# kitchenset19.net
KiCad netlist of a schematic drawn in EAGLE
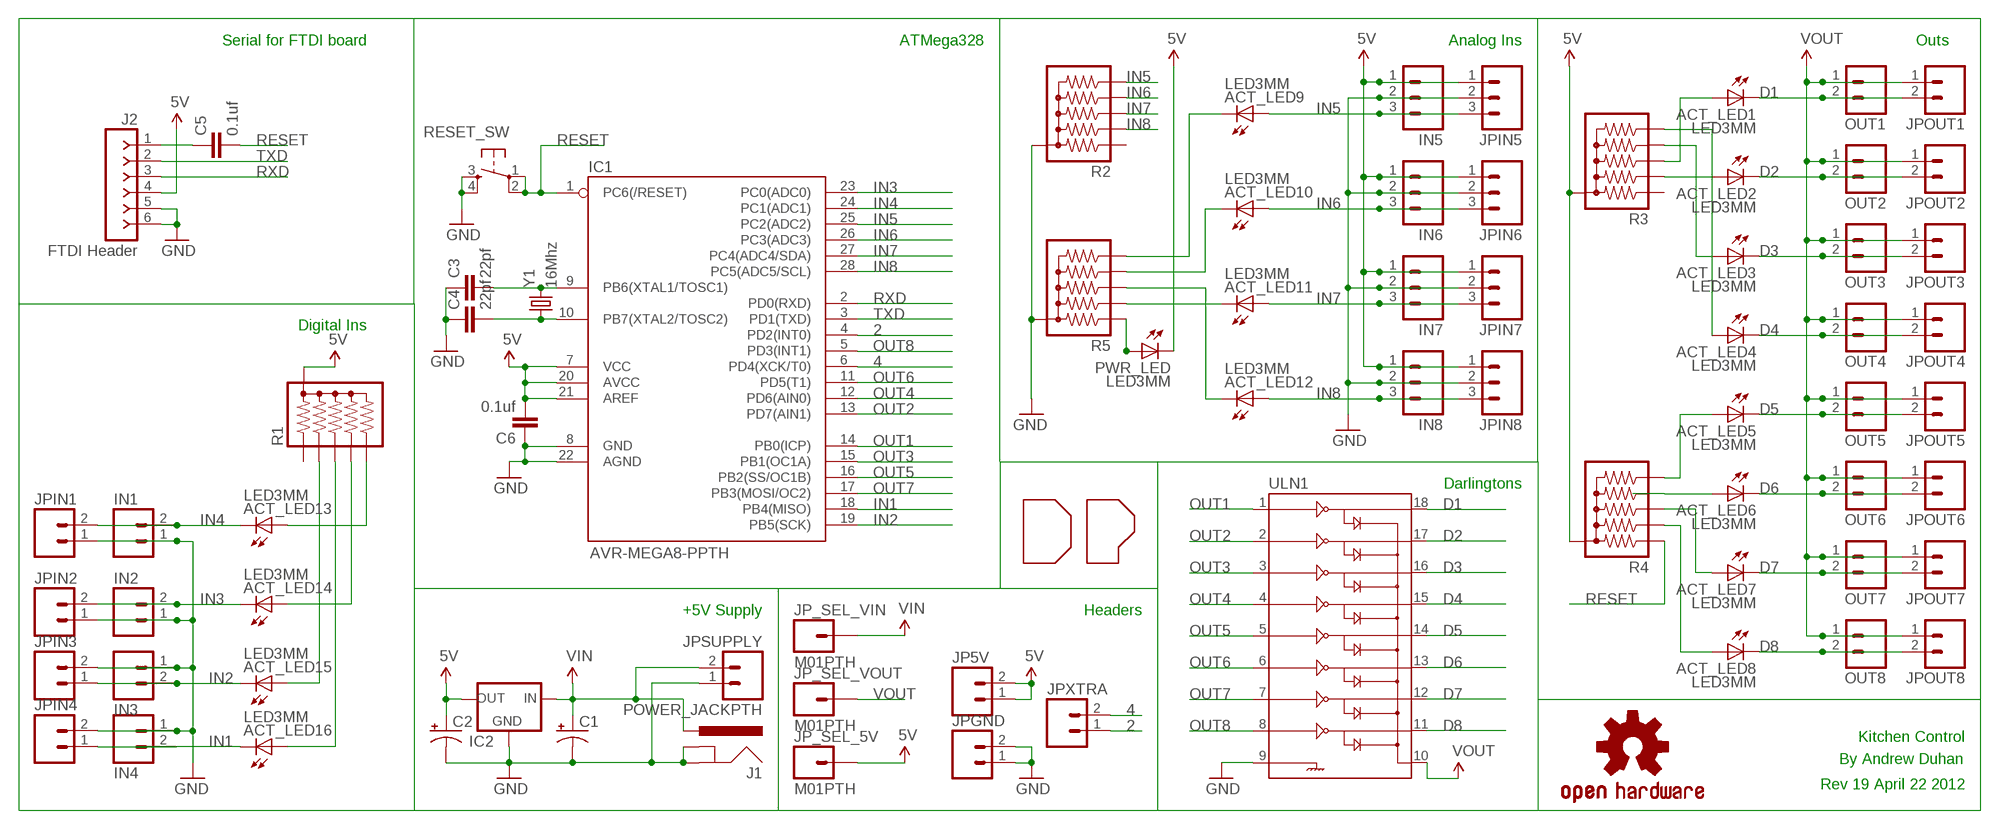
[diagram p0: schematic, sheet 1]

(export (version "E")
  (design (tool "Eeschema 10.0.6"))
  (components
    (comp (ref "ACT_LED1")
      (value "LED3MM")
      (footprint "eagle-import:LED3MM-POL")
      (libsource (lib "eagle-import") (part "LED3MM"))
    )
    (comp (ref "ACT_LED2")
      (value "LED3MM")
      (footprint "eagle-import:LED3MM-POL")
      (libsource (lib "eagle-import") (part "LED3MM"))
    )
    (comp (ref "ACT_LED3")
      (value "LED3MM")
      (footprint "eagle-import:LED3MM-POL")
      (libsource (lib "eagle-import") (part "LED3MM"))
    )
    (comp (ref "ACT_LED4")
      (value "LED3MM")
      (footprint "eagle-import:LED3MM-POL")
      (libsource (lib "eagle-import") (part "LED3MM"))
    )
    (comp (ref "ACT_LED5")
      (value "LED3MM")
      (footprint "eagle-import:LED3MM-POL")
      (libsource (lib "eagle-import") (part "LED3MM"))
    )
    (comp (ref "ACT_LED6")
      (value "LED3MM")
      (footprint "eagle-import:LED3MM-POL")
      (libsource (lib "eagle-import") (part "LED3MM"))
    )
    (comp (ref "ACT_LED7")
      (value "LED3MM")
      (footprint "eagle-import:LED3MM-POL")
      (libsource (lib "eagle-import") (part "LED3MM"))
    )
    (comp (ref "ACT_LED8")
      (value "LED3MM")
      (footprint "eagle-import:LED3MM-POL")
      (libsource (lib "eagle-import") (part "LED3MM"))
    )
    (comp (ref "ACT_LED9")
      (value "LED3MM")
      (footprint "eagle-import:LED3MM-POL")
      (libsource (lib "eagle-import") (part "LED3MM"))
    )
    (comp (ref "ACT_LED10")
      (value "LED3MM")
      (footprint "eagle-import:LED3MM-POL")
      (libsource (lib "eagle-import") (part "LED3MM"))
    )
    (comp (ref "ACT_LED11")
      (value "LED3MM")
      (footprint "eagle-import:LED3MM-POL")
      (libsource (lib "eagle-import") (part "LED3MM"))
    )
    (comp (ref "ACT_LED12")
      (value "LED3MM")
      (footprint "eagle-import:LED3MM-POL")
      (libsource (lib "eagle-import") (part "LED3MM"))
    )
    (comp (ref "ACT_LED13")
      (value "LED3MM")
      (footprint "eagle-import:LED3MM-POL")
      (libsource (lib "eagle-import") (part "LED3MM"))
    )
    (comp (ref "ACT_LED14")
      (value "LED3MM")
      (footprint "eagle-import:LED3MM-POL")
      (libsource (lib "eagle-import") (part "LED3MM"))
    )
    (comp (ref "ACT_LED15")
      (value "LED3MM")
      (footprint "eagle-import:LED3MM-POL")
      (libsource (lib "eagle-import") (part "LED3MM"))
    )
    (comp (ref "ACT_LED16")
      (value "LED3MM")
      (footprint "eagle-import:LED3MM-POL")
      (libsource (lib "eagle-import") (part "LED3MM"))
    )
    (comp (ref "C1")
      (value "CAP_POLPTH4")
      (footprint "eagle-import:CPOL-RADIAL-1000UF-25V")
      (libsource (lib "eagle-import") (part "CAP_POLPTH4"))
    )
    (comp (ref "C2")
      (value "CAP_POLPTH4")
      (footprint "eagle-import:CPOL-RADIAL-1000UF-25V")
      (libsource (lib "eagle-import") (part "CAP_POLPTH4"))
    )
    (comp (ref "C3")
      (value "22pf")
      (footprint "eagle-import:CAP-PTH-SMALL")
      (libsource (lib "eagle-import") (part "CAPPTH"))
    )
    (comp (ref "C4")
      (value "22pf")
      (footprint "eagle-import:CAP-PTH-SMALL")
      (libsource (lib "eagle-import") (part "CAPPTH"))
    )
    (comp (ref "C5")
      (value "0.1uf")
      (footprint "eagle-import:CAP-PTH-SMALL")
      (libsource (lib "eagle-import") (part "CAPPTH"))
    )
    (comp (ref "C6")
      (value "0.1uf")
      (footprint "eagle-import:CAP-PTH-SMALL")
      (libsource (lib "eagle-import") (part "CAPPTH"))
    )
    (comp (ref "IC1")
      (value "AVR-MEGA8-PPTH")
      (footprint "eagle-import:DIL28-3")
      (libsource (lib "eagle-import") (part "AVR-MEGA8-PPTH"))
    )
    (comp (ref "IC2")
      (value "V_REG_78XXSIDE")
      (footprint "eagle-import:78XXL")
      (libsource (lib "eagle-import") (part "V_REG_78XXSIDE"))
    )
    (comp (ref "IN1")
      (value "M02JST-PTH-2")
      (footprint "eagle-import:JST-2-PTH")
      (libsource (lib "eagle-import") (part "SparkFun-Connectors_M02JST-PTH-2"))
    )
    (comp (ref "IN2")
      (value "M02JST-PTH-2")
      (footprint "eagle-import:JST-2-PTH")
      (libsource (lib "eagle-import") (part "SparkFun-Connectors_M02JST-PTH-2"))
    )
    (comp (ref "IN3")
      (value "M02JST-PTH-2")
      (footprint "eagle-import:JST-2-PTH")
      (libsource (lib "eagle-import") (part "M02JST-PTH-2"))
    )
    (comp (ref "IN4")
      (value "M02JST-PTH-2")
      (footprint "eagle-import:JST-2-PTH")
      (libsource (lib "eagle-import") (part "M02JST-PTH-2"))
    )
    (comp (ref "IN5")
      (value "M03JST-PTH")
      (footprint "eagle-import:JST-3-PTH")
      (libsource (lib "eagle-import") (part "M03JST-PTH"))
    )
    (comp (ref "IN6")
      (value "M03JST-PTH")
      (footprint "eagle-import:JST-3-PTH")
      (libsource (lib "eagle-import") (part "M03JST-PTH"))
    )
    (comp (ref "IN7")
      (value "M03JST-PTH")
      (footprint "eagle-import:JST-3-PTH")
      (libsource (lib "eagle-import") (part "M03JST-PTH"))
    )
    (comp (ref "IN8")
      (value "M03JST-PTH")
      (footprint "eagle-import:JST-3-PTH")
      (libsource (lib "eagle-import") (part "M03JST-PTH"))
    )
    (comp (ref "J1")
      (value "POWER_JACKPTH")
      (footprint "eagle-import:POWER_JACK_PTH")
      (libsource (lib "eagle-import") (part "POWER_JACKPTH"))
    )
    (comp (ref "J2")
      (value "FTDI Header")
      (footprint "eagle-import:SIP-100-06-32Y")
      (libsource (lib "eagle-import") (part "F-1X06-SIP-100-32Y"))
    )
    (comp (ref "JP5V")
      (value "M02PTH")
      (footprint "eagle-import:1X02")
      (libsource (lib "eagle-import") (part "M02PTH"))
    )
    (comp (ref "JPGND")
      (value "M02PTH")
      (footprint "eagle-import:1X02")
      (libsource (lib "eagle-import") (part "M02PTH"))
    )
    (comp (ref "JPIN1")
      (value "M02PTH")
      (footprint "eagle-import:1X02")
      (libsource (lib "eagle-import") (part "SparkFun-Connectors_M02PTH"))
    )
    (comp (ref "JPIN2")
      (value "M02PTH")
      (footprint "eagle-import:1X02")
      (libsource (lib "eagle-import") (part "SparkFun-Connectors_M02PTH"))
    )
    (comp (ref "JPIN3")
      (value "M02PTH")
      (footprint "eagle-import:1X02")
      (libsource (lib "eagle-import") (part "SparkFun-Connectors_M02PTH"))
    )
    (comp (ref "JPIN4")
      (value "M02PTH")
      (footprint "eagle-import:1X02")
      (libsource (lib "eagle-import") (part "SparkFun-Connectors_M02PTH"))
    )
    (comp (ref "JPIN5")
      (value "M03PTH")
      (footprint "eagle-import:1X03")
      (libsource (lib "eagle-import") (part "SparkFun-Connectors_M03PTH"))
    )
    (comp (ref "JPIN6")
      (value "M03PTH")
      (footprint "eagle-import:1X03")
      (libsource (lib "eagle-import") (part "SparkFun-Connectors_M03PTH"))
    )
    (comp (ref "JPIN7")
      (value "M03PTH")
      (footprint "eagle-import:1X03")
      (libsource (lib "eagle-import") (part "SparkFun-Connectors_M03PTH"))
    )
    (comp (ref "JPIN8")
      (value "M03PTH")
      (footprint "eagle-import:1X03")
      (libsource (lib "eagle-import") (part "SparkFun-Connectors_M03PTH"))
    )
    (comp (ref "JPOUT1")
      (value "M02PTH")
      (footprint "eagle-import:1X02")
      (libsource (lib "eagle-import") (part "SparkFun-Connectors_M02PTH"))
    )
    (comp (ref "JPOUT2")
      (value "M02PTH")
      (footprint "eagle-import:1X02")
      (libsource (lib "eagle-import") (part "SparkFun-Connectors_M02PTH"))
    )
    (comp (ref "JPOUT3")
      (value "M02PTH")
      (footprint "eagle-import:1X02")
      (libsource (lib "eagle-import") (part "SparkFun-Connectors_M02PTH"))
    )
    (comp (ref "JPOUT4")
      (value "M02PTH")
      (footprint "eagle-import:1X02")
      (libsource (lib "eagle-import") (part "SparkFun-Connectors_M02PTH"))
    )
    (comp (ref "JPOUT5")
      (value "M02PTH")
      (footprint "eagle-import:1X02")
      (libsource (lib "eagle-import") (part "SparkFun-Connectors_M02PTH"))
    )
    (comp (ref "JPOUT6")
      (value "M02PTH")
      (footprint "eagle-import:1X02")
      (libsource (lib "eagle-import") (part "SparkFun-Connectors_M02PTH"))
    )
    (comp (ref "JPOUT7")
      (value "M02PTH")
      (footprint "eagle-import:1X02")
      (libsource (lib "eagle-import") (part "SparkFun-Connectors_M02PTH"))
    )
    (comp (ref "JPOUT8")
      (value "M02PTH")
      (footprint "eagle-import:1X02")
      (libsource (lib "eagle-import") (part "SparkFun-Connectors_M02PTH"))
    )
    (comp (ref "JPSUPPLY")
      (value "M02PTH4")
      (footprint "eagle-import:1X02_XTRA_BIG")
      (libsource (lib "eagle-import") (part "M02PTH4"))
    )
    (comp (ref "JPXTRA")
      (value "M02PTH")
      (footprint "eagle-import:1X02")
      (libsource (lib "eagle-import") (part "M02PTH"))
    )
    (comp (ref "JP_SEL_5V")
      (value "M01PTH")
      (footprint "eagle-import:1X01")
      (libsource (lib "eagle-import") (part "M01PTH"))
    )
    (comp (ref "JP_SEL_VIN")
      (value "M01PTH")
      (footprint "eagle-import:1X01")
      (libsource (lib "eagle-import") (part "M01PTH"))
    )
    (comp (ref "JP_SEL_VOUT")
      (value "M01PTH")
      (footprint "eagle-import:1X01")
      (libsource (lib "eagle-import") (part "M01PTH"))
    )
    (comp (ref "OUT1")
      (value "M02JST-PTH-2")
      (footprint "eagle-import:JST-2-PTH")
      (libsource (lib "eagle-import") (part "M02JST-PTH-2"))
    )
    (comp (ref "OUT2")
      (value "M02JST-PTH-2")
      (footprint "eagle-import:JST-2-PTH")
      (libsource (lib "eagle-import") (part "M02JST-PTH-2"))
    )
    (comp (ref "OUT3")
      (value "M02JST-PTH-2")
      (footprint "eagle-import:JST-2-PTH")
      (libsource (lib "eagle-import") (part "M02JST-PTH-2"))
    )
    (comp (ref "OUT4")
      (value "M02JST-PTH-2")
      (footprint "eagle-import:JST-2-PTH")
      (libsource (lib "eagle-import") (part "M02JST-PTH-2"))
    )
    (comp (ref "OUT5")
      (value "M02JST-PTH-2")
      (footprint "eagle-import:JST-2-PTH")
      (libsource (lib "eagle-import") (part "M02JST-PTH-2"))
    )
    (comp (ref "OUT6")
      (value "M02JST-PTH-2")
      (footprint "eagle-import:JST-2-PTH")
      (libsource (lib "eagle-import") (part "M02JST-PTH-2"))
    )
    (comp (ref "OUT7")
      (value "M02JST-PTH-2")
      (footprint "eagle-import:JST-2-PTH")
      (libsource (lib "eagle-import") (part "M02JST-PTH-2"))
    )
    (comp (ref "OUT8")
      (value "M02JST-PTH-2")
      (footprint "eagle-import:JST-2-PTH")
      (libsource (lib "eagle-import") (part "M02JST-PTH-2"))
    )
    (comp (ref "PWR_LED")
      (value "LED3MM")
      (footprint "eagle-import:LED3MM-POL")
      (libsource (lib "eagle-import") (part "LED3MM"))
    )
    (comp (ref "R1")
      (value "RPACK-BUSSED-SIP-PTH-5")
      (footprint "eagle-import:RPACK-SIP-PTH-5")
      (libsource (lib "eagle-import") (part "RPACK-BUSSED-SIP-PTH-5"))
    )
    (comp (ref "R2")
      (value "RPACK-BUSSED-SIP-PTH-5")
      (footprint "eagle-import:RPACK-SIP-PTH-5")
      (libsource (lib "eagle-import") (part "RPACK-BUSSED-SIP-PTH-5"))
    )
    (comp (ref "R3")
      (value "RPACK-BUSSED-SIP-PTH-5")
      (footprint "eagle-import:RPACK-SIP-PTH-5")
      (libsource (lib "eagle-import") (part "RPACK-BUSSED-SIP-PTH-5"))
    )
    (comp (ref "R4")
      (value "RPACK-BUSSED-SIP-PTH-5")
      (footprint "eagle-import:RPACK-SIP-PTH-5")
      (libsource (lib "eagle-import") (part "RPACK-BUSSED-SIP-PTH-5"))
    )
    (comp (ref "R5")
      (value "RPACK-BUSSED-SIP-PTH-5")
      (footprint "eagle-import:RPACK-SIP-PTH-5")
      (libsource (lib "eagle-import") (part "RPACK-BUSSED-SIP-PTH-5"))
    )
    (comp (ref "RESET_SW")
      (value "TAC_SWITCHPTH")
      (footprint "eagle-import:TACTILE-PTH")
      (libsource (lib "eagle-import") (part "TAC_SWITCHPTH"))
    )
    (comp (ref "U$1")
      (value "OSHW-LOGOM")
      (footprint "eagle-import:OSHW-LOGO-M")
      (libsource (lib "eagle-import") (part "OSHW-LOGOM"))
    )
    (comp (ref "U$9")
      (value "DP_LOGO")
      (footprint "eagle-import:DP_LOGO")
      (libsource (lib "eagle-import") (part "DP_LOGO"))
    )
    (comp (ref "ULN1")
      (value "ULN2803DIP")
      (footprint "eagle-import:DIL18")
      (libsource (lib "eagle-import") (part "ULN2803DIP"))
    )
    (comp (ref "Y1")
      (value "16Mhz")
      (footprint "eagle-import:HC49US")
      (libsource (lib "eagle-import") (part "CRYSTALHC49US"))
    )
  )
  (nets
    (net (code "1") (name "/2") (class "Default")
      (node (ref "IC1") (pin "4") (pinfunction "PD2(INT0)_4") (pintype "bidirectional"))
      (node (ref "JPXTRA") (pin "1") (pinfunction "1_1") (pintype "passive"))
    )
    (net (code "2") (name "/4") (class "Default")
      (node (ref "IC1") (pin "6") (pinfunction "PD4(XCK/T0)_6") (pintype "bidirectional"))
      (node (ref "JPXTRA") (pin "2") (pinfunction "2_2") (pintype "passive"))
    )
    (net (code "3") (name "/D1") (class "Default")
      (node (ref "ACT_LED1") (pin "K") (pinfunction "C_K") (pintype "passive"))
      (node (ref "JPOUT1") (pin "2") (pinfunction "2_2") (pintype "passive"))
      (node (ref "OUT1") (pin "2") (pinfunction "2_2") (pintype "passive"))
      (node (ref "ULN1") (pin "18") (pinfunction "18_18") (pintype "bidirectional"))
    )
    (net (code "4") (name "/D2") (class "Default")
      (node (ref "ACT_LED2") (pin "K") (pinfunction "C_K") (pintype "passive"))
      (node (ref "JPOUT2") (pin "2") (pinfunction "2_2") (pintype "passive"))
      (node (ref "OUT2") (pin "2") (pinfunction "2_2") (pintype "passive"))
      (node (ref "ULN1") (pin "17") (pinfunction "17_17") (pintype "bidirectional"))
    )
    (net (code "5") (name "/D3") (class "Default")
      (node (ref "ACT_LED3") (pin "K") (pinfunction "C_K") (pintype "passive"))
      (node (ref "JPOUT3") (pin "2") (pinfunction "2_2") (pintype "passive"))
      (node (ref "OUT3") (pin "2") (pinfunction "2_2") (pintype "passive"))
      (node (ref "ULN1") (pin "16") (pinfunction "16_16") (pintype "bidirectional"))
    )
    (net (code "6") (name "/D4") (class "Default")
      (node (ref "ACT_LED4") (pin "K") (pinfunction "C_K") (pintype "passive"))
      (node (ref "JPOUT4") (pin "2") (pinfunction "2_2") (pintype "passive"))
      (node (ref "OUT4") (pin "2") (pinfunction "2_2") (pintype "passive"))
      (node (ref "ULN1") (pin "15") (pinfunction "15_15") (pintype "bidirectional"))
    )
    (net (code "7") (name "/D5") (class "Default")
      (node (ref "ACT_LED5") (pin "K") (pinfunction "C_K") (pintype "passive"))
      (node (ref "JPOUT5") (pin "2") (pinfunction "2_2") (pintype "passive"))
      (node (ref "OUT5") (pin "2") (pinfunction "2_2") (pintype "passive"))
      (node (ref "ULN1") (pin "14") (pinfunction "14_14") (pintype "bidirectional"))
    )
    (net (code "8") (name "/D6") (class "Default")
      (node (ref "ACT_LED6") (pin "K") (pinfunction "C_K") (pintype "passive"))
      (node (ref "JPOUT6") (pin "2") (pinfunction "2_2") (pintype "passive"))
      (node (ref "OUT6") (pin "2") (pinfunction "2_2") (pintype "passive"))
      (node (ref "ULN1") (pin "13") (pinfunction "13_13") (pintype "bidirectional"))
    )
    (net (code "9") (name "/D7") (class "Default")
      (node (ref "ACT_LED7") (pin "K") (pinfunction "C_K") (pintype "passive"))
      (node (ref "JPOUT7") (pin "2") (pinfunction "2_2") (pintype "passive"))
      (node (ref "OUT7") (pin "2") (pinfunction "2_2") (pintype "passive"))
      (node (ref "ULN1") (pin "12") (pinfunction "12_12") (pintype "bidirectional"))
    )
    (net (code "10") (name "/D8") (class "Default")
      (node (ref "ACT_LED8") (pin "K") (pinfunction "C_K") (pintype "passive"))
      (node (ref "JPOUT8") (pin "2") (pinfunction "2_2") (pintype "passive"))
      (node (ref "OUT8") (pin "2") (pinfunction "2_2") (pintype "passive"))
      (node (ref "ULN1") (pin "11") (pinfunction "11_11") (pintype "bidirectional"))
    )
    (net (code "11") (name "/IN1") (class "Default")
      (node (ref "ACT_LED16") (pin "K") (pinfunction "C_K") (pintype "passive"))
      (node (ref "IC1") (pin "18") (pinfunction "PB4(MISO)_18") (pintype "bidirectional"))
      (node (ref "IN4") (pin "2") (pinfunction "2_2") (pintype "passive"))
      (node (ref "JPIN4") (pin "1") (pinfunction "1_1") (pintype "passive"))
    )
    (net (code "12") (name "/IN2") (class "Default")
      (node (ref "ACT_LED15") (pin "K") (pinfunction "C_K") (pintype "passive"))
      (node (ref "IC1") (pin "19") (pinfunction "PB5(SCK)_19") (pintype "bidirectional"))
      (node (ref "IN3") (pin "2") (pinfunction "2_2") (pintype "passive"))
      (node (ref "JPIN3") (pin "1") (pinfunction "1_1") (pintype "passive"))
    )
    (net (code "13") (name "/IN3") (class "Default")
      (node (ref "ACT_LED14") (pin "K") (pinfunction "C_K") (pintype "passive"))
      (node (ref "IC1") (pin "23") (pinfunction "PC0(ADC0)_23") (pintype "bidirectional"))
      (node (ref "IN2") (pin "2") (pinfunction "2_2") (pintype "passive"))
      (node (ref "JPIN2") (pin "2") (pinfunction "2_2") (pintype "passive"))
    )
    (net (code "14") (name "/IN4") (class "Default")
      (node (ref "ACT_LED13") (pin "K") (pinfunction "C_K") (pintype "passive"))
      (node (ref "IC1") (pin "24") (pinfunction "PC1(ADC1)_24") (pintype "bidirectional"))
      (node (ref "IN1") (pin "2") (pinfunction "2_2") (pintype "passive"))
      (node (ref "JPIN1") (pin "2") (pinfunction "2_2") (pintype "passive"))
    )
    (net (code "15") (name "/IN5") (class "Default")
      (node (ref "ACT_LED9") (pin "A") (pinfunction "A_A") (pintype "passive"))
      (node (ref "IC1") (pin "25") (pinfunction "PC2(ADC2)_25") (pintype "bidirectional"))
      (node (ref "IN5") (pin "3") (pinfunction "3_3") (pintype "passive"))
      (node (ref "JPIN5") (pin "3") (pinfunction "3_3") (pintype "passive"))
      (node (ref "R2") (pin "P$6") (pinfunction "6_P$6") (pintype "passive"))
    )
    (net (code "16") (name "/IN6") (class "Default")
      (node (ref "ACT_LED10") (pin "A") (pinfunction "A_A") (pintype "passive"))
      (node (ref "IC1") (pin "26") (pinfunction "PC3(ADC3)_26") (pintype "bidirectional"))
      (node (ref "IN6") (pin "3") (pinfunction "3_3") (pintype "passive"))
      (node (ref "JPIN6") (pin "3") (pinfunction "3_3") (pintype "passive"))
      (node (ref "R2") (pin "P$5") (pinfunction "5_P$5") (pintype "passive"))
    )
    (net (code "17") (name "/IN7") (class "Default")
      (node (ref "ACT_LED11") (pin "A") (pinfunction "A_A") (pintype "passive"))
      (node (ref "IC1") (pin "27") (pinfunction "PC4(ADC4/SDA)_27") (pintype "bidirectional"))
      (node (ref "IN7") (pin "3") (pinfunction "3_3") (pintype "passive"))
      (node (ref "JPIN7") (pin "3") (pinfunction "3_3") (pintype "passive"))
      (node (ref "R2") (pin "P$4") (pinfunction "4_P$4") (pintype "passive"))
    )
    (net (code "18") (name "/IN8") (class "Default")
      (node (ref "ACT_LED12") (pin "A") (pinfunction "A_A") (pintype "passive"))
      (node (ref "IC1") (pin "28") (pinfunction "PC5(ADC5/SCL)_28") (pintype "bidirectional"))
      (node (ref "IN8") (pin "3") (pinfunction "3_3") (pintype "passive"))
      (node (ref "JPIN8") (pin "3") (pinfunction "3_3") (pintype "passive"))
      (node (ref "R2") (pin "P$3") (pinfunction "3_P$3") (pintype "passive"))
    )
    (net (code "19") (name "/OUT1") (class "Default")
      (node (ref "IC1") (pin "14") (pinfunction "PB0(ICP)_14") (pintype "bidirectional"))
      (node (ref "ULN1") (pin "1") (pinfunction "1_1") (pintype "bidirectional"))
    )
    (net (code "20") (name "/OUT2") (class "Default")
      (node (ref "IC1") (pin "13") (pinfunction "PD7(AIN1)_13") (pintype "bidirectional"))
      (node (ref "ULN1") (pin "2") (pinfunction "2_2") (pintype "bidirectional"))
    )
    (net (code "21") (name "/OUT3") (class "Default")
      (node (ref "IC1") (pin "15") (pinfunction "PB1(OC1A)_15") (pintype "bidirectional"))
      (node (ref "ULN1") (pin "3") (pinfunction "3_3") (pintype "bidirectional"))
    )
    (net (code "22") (name "/OUT4") (class "Default")
      (node (ref "IC1") (pin "12") (pinfunction "PD6(AIN0)_12") (pintype "bidirectional"))
      (node (ref "ULN1") (pin "4") (pinfunction "4_4") (pintype "bidirectional"))
    )
    (net (code "23") (name "/OUT5") (class "Default")
      (node (ref "IC1") (pin "16") (pinfunction "PB2(SS/OC1B)_16") (pintype "bidirectional"))
      (node (ref "ULN1") (pin "5") (pinfunction "5_5") (pintype "bidirectional"))
    )
    (net (code "24") (name "/OUT6") (class "Default")
      (node (ref "IC1") (pin "11") (pinfunction "PD5(T1)_11") (pintype "bidirectional"))
      (node (ref "ULN1") (pin "6") (pinfunction "6_6") (pintype "bidirectional"))
    )
    (net (code "25") (name "/OUT7") (class "Default")
      (node (ref "IC1") (pin "17") (pinfunction "PB3(MOSI/OC2)_17") (pintype "bidirectional"))
      (node (ref "ULN1") (pin "7") (pinfunction "7_7") (pintype "bidirectional"))
    )
    (net (code "26") (name "/OUT8") (class "Default")
      (node (ref "IC1") (pin "5") (pinfunction "PD3(INT1)_5") (pintype "bidirectional"))
      (node (ref "ULN1") (pin "8") (pinfunction "8_8") (pintype "bidirectional"))
    )
    (net (code "27") (name "/RESET") (class "Default")
      (node (ref "C5") (pin "2") (pinfunction "2_2") (pintype "passive"))
      (node (ref "IC1") (pin "1") (pinfunction "PC6(/RESET)_1") (pintype "bidirectional"))
      (node (ref "R4") (pin "P$2") (pinfunction "2_P$2") (pintype "passive"))
      (node (ref "RESET_SW") (pin "1") (pinfunction "1_1") (pintype "passive"))
      (node (ref "RESET_SW") (pin "2") (pinfunction "2_2") (pintype "passive"))
    )
    (net (code "28") (name "/RXD") (class "Default")
      (node (ref "IC1") (pin "2") (pinfunction "PD0(RXD)_2") (pintype "bidirectional"))
      (node (ref "J2") (pin "3") (pinfunction "3_3") (pintype "passive"))
    )
    (net (code "29") (name "/TXD") (class "Default")
      (node (ref "IC1") (pin "3") (pinfunction "PD1(TXD)_3") (pintype "bidirectional"))
      (node (ref "J2") (pin "2") (pinfunction "2_2") (pintype "passive"))
    )
    (net (code "30") (name "5V") (class "Default")
      (node (ref "C2") (pin "1") (pinfunction "+_1") (pintype "passive"))
      (node (ref "C6") (pin "2") (pinfunction "2_2") (pintype "passive"))
      (node (ref "IC1") (pin "20") (pinfunction "AVCC_20") (pintype "bidirectional"))
      (node (ref "IC1") (pin "21") (pinfunction "AREF_21") (pintype "bidirectional"))
      (node (ref "IC1") (pin "7") (pinfunction "VCC_7") (pintype "bidirectional"))
      (node (ref "IC2") (pin "OUT") (pinfunction "OUT_OUT") (pintype "output"))
      (node (ref "IN5") (pin "1") (pinfunction "1_1") (pintype "passive"))
      (node (ref "IN6") (pin "1") (pinfunction "1_1") (pintype "passive"))
      (node (ref "IN7") (pin "1") (pinfunction "1_1") (pintype "passive"))
      (node (ref "IN8") (pin "1") (pinfunction "1_1") (pintype "passive"))
      (node (ref "J2") (pin "4") (pinfunction "4_4") (pintype "passive"))
      (node (ref "JP5V") (pin "1") (pinfunction "1_1") (pintype "passive"))
      (node (ref "JP5V") (pin "2") (pinfunction "2_2") (pintype "passive"))
      (node (ref "JPIN5") (pin "1") (pinfunction "1_1") (pintype "passive"))
      (node (ref "JPIN6") (pin "1") (pinfunction "1_1") (pintype "passive"))
      (node (ref "JPIN7") (pin "1") (pinfunction "1_1") (pintype "passive"))
      (node (ref "JPIN8") (pin "1") (pinfunction "1_1") (pintype "passive"))
      (node (ref "JP_SEL_5V") (pin "1") (pinfunction "1_1") (pintype "passive"))
      (node (ref "PWR_LED") (pin "K") (pinfunction "C_K") (pintype "passive"))
      (node (ref "R1") (pin "P$1") (pinfunction "1_P$1") (pintype "passive"))
      (node (ref "R3") (pin "P$1") (pinfunction "1_P$1") (pintype "passive"))
      (node (ref "R4") (pin "P$1") (pinfunction "1_P$1") (pintype "passive"))
    )
    (net (code "31") (name "GND") (class "Default")
      (node (ref "C1") (pin "2") (pinfunction "-_2") (pintype "passive"))
      (node (ref "C2") (pin "2") (pinfunction "-_2") (pintype "passive"))
      (node (ref "C3") (pin "1") (pinfunction "1_1") (pintype "passive"))
      (node (ref "C4") (pin "1") (pinfunction "1_1") (pintype "passive"))
      (node (ref "C6") (pin "1") (pinfunction "1_1") (pintype "passive"))
      (node (ref "IC1") (pin "22") (pinfunction "AGND_22") (pintype "bidirectional"))
      (node (ref "IC1") (pin "8") (pinfunction "GND_8") (pintype "bidirectional"))
      (node (ref "IC2") (pin "GND") (pinfunction "GND_GND") (pintype "input"))
      (node (ref "IN1") (pin "1") (pinfunction "1_1") (pintype "passive"))
      (node (ref "IN2") (pin "1") (pinfunction "1_1") (pintype "passive"))
      (node (ref "IN3") (pin "1") (pinfunction "1_1") (pintype "passive"))
      (node (ref "IN4") (pin "1") (pinfunction "1_1") (pintype "passive"))
      (node (ref "IN5") (pin "2") (pinfunction "2_2") (pintype "passive"))
      (node (ref "IN6") (pin "2") (pinfunction "2_2") (pintype "passive"))
      (node (ref "IN7") (pin "2") (pinfunction "2_2") (pintype "passive"))
      (node (ref "IN8") (pin "2") (pinfunction "2_2") (pintype "passive"))
      (node (ref "J1") (pin "GND") (pinfunction "GND_GND") (pintype "bidirectional"))
      (node (ref "J1") (pin "GNDBREAK") (pinfunction "GNDBREAK_GNDBREAK") (pintype "bidirectional"))
      (node (ref "J2") (pin "5") (pinfunction "5_5") (pintype "passive"))
      (node (ref "J2") (pin "6") (pinfunction "6_6") (pintype "passive"))
      (node (ref "JPGND") (pin "1") (pinfunction "1_1") (pintype "passive"))
      (node (ref "JPGND") (pin "2") (pinfunction "2_2") (pintype "passive"))
      (node (ref "JPIN1") (pin "1") (pinfunction "1_1") (pintype "passive"))
      (node (ref "JPIN2") (pin "1") (pinfunction "1_1") (pintype "passive"))
      (node (ref "JPIN3") (pin "2") (pinfunction "2_2") (pintype "passive"))
      (node (ref "JPIN4") (pin "2") (pinfunction "2_2") (pintype "passive"))
      (node (ref "JPIN5") (pin "2") (pinfunction "2_2") (pintype "passive"))
      (node (ref "JPIN6") (pin "2") (pinfunction "2_2") (pintype "passive"))
      (node (ref "JPIN7") (pin "2") (pinfunction "2_2") (pintype "passive"))
      (node (ref "JPIN8") (pin "2") (pinfunction "2_2") (pintype "passive"))
      (node (ref "JPSUPPLY") (pin "1") (pinfunction "1_1") (pintype "passive"))
      (node (ref "R2") (pin "P$1") (pinfunction "1_P$1") (pintype "passive"))
      (node (ref "R5") (pin "P$1") (pinfunction "1_P$1") (pintype "passive"))
      (node (ref "RESET_SW") (pin "3") (pinfunction "3_3") (pintype "passive"))
      (node (ref "RESET_SW") (pin "4") (pinfunction "4_4") (pintype "passive"))
      (node (ref "ULN1") (pin "9") (pinfunction "9_9") (pintype "bidirectional"))
    )
    (net (code "32") (name "Net-(ACT_LED9-C)") (class "Default")
      (node (ref "ACT_LED9") (pin "K") (pinfunction "C_K") (pintype "passive"))
      (node (ref "R5") (pin "P$6") (pinfunction "6_P$6") (pintype "passive"))
    )
    (net (code "33") (name "Net-(ACT_LED10-C)") (class "Default")
      (node (ref "ACT_LED10") (pin "K") (pinfunction "C_K") (pintype "passive"))
      (node (ref "R5") (pin "P$5") (pinfunction "5_P$5") (pintype "passive"))
    )
    (net (code "34") (name "Net-(ACT_LED11-C)") (class "Default")
      (node (ref "ACT_LED11") (pin "K") (pinfunction "C_K") (pintype "passive"))
      (node (ref "R5") (pin "P$3") (pinfunction "3_P$3") (pintype "passive"))
    )
    (net (code "35") (name "Net-(ACT_LED12-C)") (class "Default")
      (node (ref "ACT_LED12") (pin "K") (pinfunction "C_K") (pintype "passive"))
      (node (ref "R5") (pin "P$4") (pinfunction "4_P$4") (pintype "passive"))
    )
    (net (code "36") (name "Net-(C5-Pad1)") (class "Default")
      (node (ref "C5") (pin "1") (pinfunction "1_1") (pintype "passive"))
      (node (ref "J2") (pin "1") (pinfunction "1_1") (pintype "passive"))
    )
    (net (code "37") (name "Net-(IC1-PB6(XTAL1{slash}TOSC1))") (class "Default")
      (node (ref "C3") (pin "2") (pinfunction "2_2") (pintype "passive"))
      (node (ref "IC1") (pin "9") (pinfunction "PB6(XTAL1/TOSC1)_9") (pintype "bidirectional"))
      (node (ref "Y1") (pin "2") (pinfunction "2_2") (pintype "passive"))
    )
    (net (code "38") (name "Net-(IC1-PB7(XTAL2{slash}TOSC2))") (class "Default")
      (node (ref "C4") (pin "2") (pinfunction "2_2") (pintype "passive"))
      (node (ref "IC1") (pin "10") (pinfunction "PB7(XTAL2/TOSC2)_10") (pintype "bidirectional"))
      (node (ref "Y1") (pin "1") (pinfunction "1_1") (pintype "passive"))
    )
    (net (code "39") (name "Net-(R1-3)") (class "Default")
      (node (ref "ACT_LED15") (pin "A") (pinfunction "A_A") (pintype "passive"))
      (node (ref "R1") (pin "P$3") (pinfunction "3_P$3") (pintype "passive"))
    )
    (net (code "40") (name "Net-(R1-4)") (class "Default")
      (node (ref "ACT_LED16") (pin "A") (pinfunction "A_A") (pintype "passive"))
      (node (ref "R1") (pin "P$4") (pinfunction "4_P$4") (pintype "passive"))
    )
    (net (code "41") (name "Net-(R1-5)") (class "Default")
      (node (ref "ACT_LED14") (pin "A") (pinfunction "A_A") (pintype "passive"))
      (node (ref "R1") (pin "P$5") (pinfunction "5_P$5") (pintype "passive"))
    )
    (net (code "42") (name "Net-(R1-6)") (class "Default")
      (node (ref "ACT_LED13") (pin "A") (pinfunction "A_A") (pintype "passive"))
      (node (ref "R1") (pin "P$6") (pinfunction "6_P$6") (pintype "passive"))
    )
    (net (code "43") (name "Net-(R3-3)") (class "Default")
      (node (ref "ACT_LED2") (pin "A") (pinfunction "A_A") (pintype "passive"))
      (node (ref "R3") (pin "P$3") (pinfunction "3_P$3") (pintype "passive"))
    )
    (net (code "44") (name "Net-(R3-4)") (class "Default")
      (node (ref "ACT_LED1") (pin "A") (pinfunction "A_A") (pintype "passive"))
      (node (ref "R3") (pin "P$4") (pinfunction "4_P$4") (pintype "passive"))
    )
    (net (code "45") (name "Net-(R3-5)") (class "Default")
      (node (ref "ACT_LED3") (pin "A") (pinfunction "A_A") (pintype "passive"))
      (node (ref "R3") (pin "P$5") (pinfunction "5_P$5") (pintype "passive"))
    )
    (net (code "46") (name "Net-(R3-6)") (class "Default")
      (node (ref "ACT_LED4") (pin "A") (pinfunction "A_A") (pintype "passive"))
      (node (ref "R3") (pin "P$6") (pinfunction "6_P$6") (pintype "passive"))
    )
    (net (code "47") (name "Net-(R4-3)") (class "Default")
      (node (ref "ACT_LED8") (pin "A") (pinfunction "A_A") (pintype "passive"))
      (node (ref "R4") (pin "P$3") (pinfunction "3_P$3") (pintype "passive"))
    )
    (net (code "48") (name "Net-(R4-4)") (class "Default")
      (node (ref "ACT_LED7") (pin "A") (pinfunction "A_A") (pintype "passive"))
      (node (ref "R4") (pin "P$4") (pinfunction "4_P$4") (pintype "passive"))
    )
    (net (code "49") (name "Net-(R4-5)") (class "Default")
      (node (ref "ACT_LED6") (pin "A") (pinfunction "A_A") (pintype "passive"))
      (node (ref "R4") (pin "P$5") (pinfunction "5_P$5") (pintype "passive"))
    )
    (net (code "50") (name "Net-(R4-6)") (class "Default")
      (node (ref "ACT_LED5") (pin "A") (pinfunction "A_A") (pintype "passive"))
      (node (ref "R4") (pin "P$6") (pinfunction "6_P$6") (pintype "passive"))
    )
    (net (code "51") (name "Net-(R5-2)") (class "Default")
      (node (ref "PWR_LED") (pin "A") (pinfunction "A_A") (pintype "passive"))
      (node (ref "R5") (pin "P$2") (pinfunction "2_P$2") (pintype "passive"))
    )
    (net (code "52") (name "VIN") (class "Default")
      (node (ref "C1") (pin "1") (pinfunction "+_1") (pintype "passive"))
      (node (ref "IC2") (pin "IN") (pinfunction "IN_IN") (pintype "input"))
      (node (ref "J1") (pin "PWR") (pinfunction "PWR_PWR") (pintype "bidirectional"))
      (node (ref "JPSUPPLY") (pin "2") (pinfunction "2_2") (pintype "passive"))
      (node (ref "JP_SEL_VIN") (pin "1") (pinfunction "1_1") (pintype "passive"))
    )
    (net (code "53") (name "VOUT") (class "Default")
      (node (ref "JPOUT1") (pin "1") (pinfunction "1_1") (pintype "passive"))
      (node (ref "JPOUT2") (pin "1") (pinfunction "1_1") (pintype "passive"))
      (node (ref "JPOUT3") (pin "1") (pinfunction "1_1") (pintype "passive"))
      (node (ref "JPOUT4") (pin "1") (pinfunction "1_1") (pintype "passive"))
      (node (ref "JPOUT5") (pin "1") (pinfunction "1_1") (pintype "passive"))
      (node (ref "JPOUT6") (pin "1") (pinfunction "1_1") (pintype "passive"))
      (node (ref "JPOUT7") (pin "1") (pinfunction "1_1") (pintype "passive"))
      (node (ref "JPOUT8") (pin "1") (pinfunction "1_1") (pintype "passive"))
      (node (ref "JP_SEL_VOUT") (pin "1") (pinfunction "1_1") (pintype "passive"))
      (node (ref "OUT1") (pin "1") (pinfunction "1_1") (pintype "passive"))
      (node (ref "OUT2") (pin "1") (pinfunction "1_1") (pintype "passive"))
      (node (ref "OUT3") (pin "1") (pinfunction "1_1") (pintype "passive"))
      (node (ref "OUT4") (pin "1") (pinfunction "1_1") (pintype "passive"))
      (node (ref "OUT5") (pin "1") (pinfunction "1_1") (pintype "passive"))
      (node (ref "OUT6") (pin "1") (pinfunction "1_1") (pintype "passive"))
      (node (ref "OUT7") (pin "1") (pinfunction "1_1") (pintype "passive"))
      (node (ref "OUT8") (pin "1") (pinfunction "1_1") (pintype "passive"))
      (node (ref "ULN1") (pin "10") (pinfunction "10_10") (pintype "bidirectional"))
    )
    (net (code "54") (name "unconnected-(R1-2-PadP$2)") (class "Default")
      (node (ref "R1") (pin "P$2") (pinfunction "2_P$2") (pintype "passive"))
    )
    (net (code "55") (name "unconnected-(R2-2-PadP$2)") (class "Default")
      (node (ref "R2") (pin "P$2") (pinfunction "2_P$2") (pintype "passive"))
    )
    (net (code "56") (name "unconnected-(R3-2-PadP$2)") (class "Default")
      (node (ref "R3") (pin "P$2") (pinfunction "2_P$2") (pintype "passive"))
    )
  )
)
